# CLK_PWR.net
KiCad netlist of a schematic drawn in Altium Designer
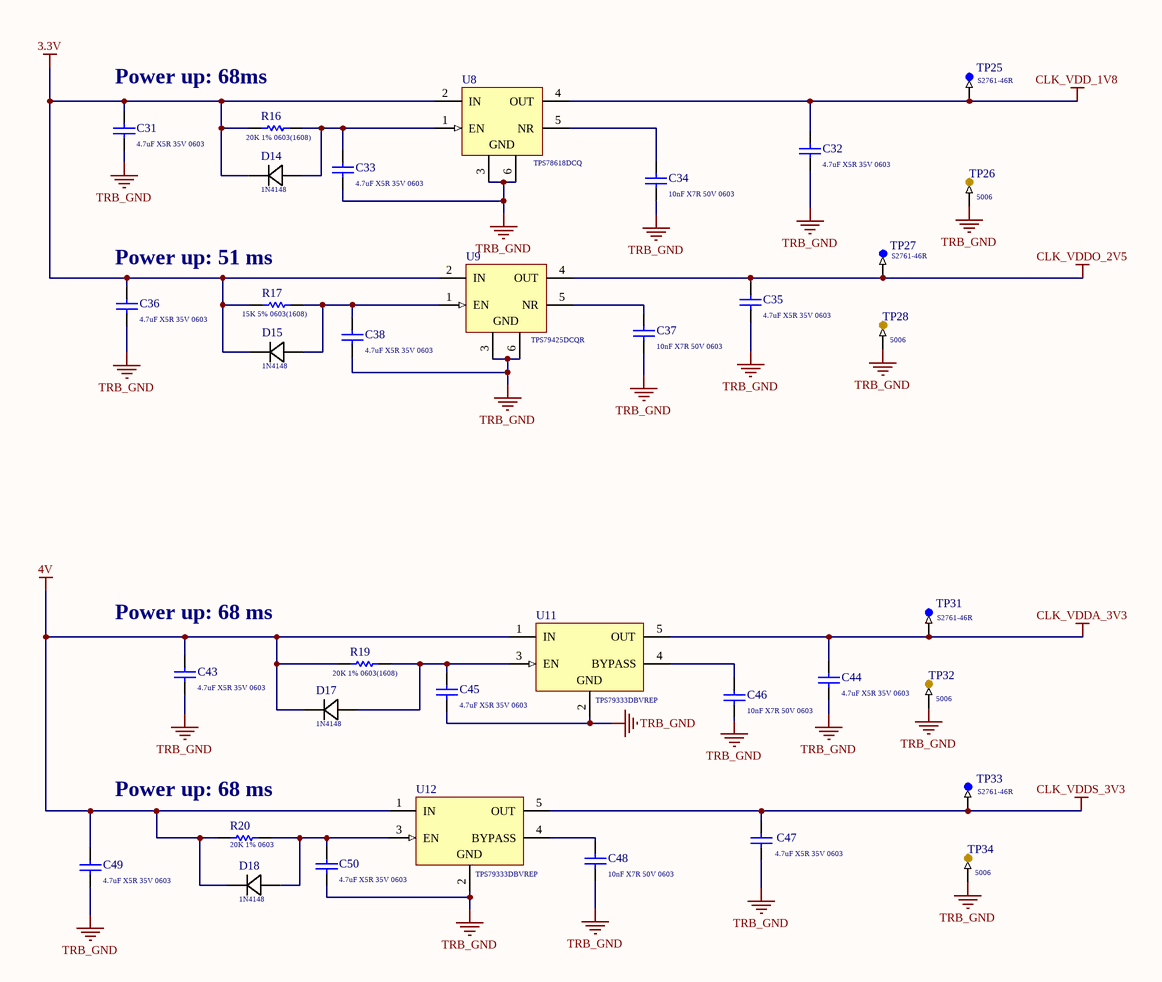
[diagram p0: CLK_PWR.SchDoc]

(export (version "E")
  (design (tool "Eeschema 10.0.6"))
  (components
    (comp (ref "C31")
      (value "Cap_Murata_ZRB18AR6YA475ME05L_4.7uF")
      (footprint "Cap_Murata_ZRB18AR6YA475ME05L_4.7uF")
      (description "CAP CER 4.7uF 35V X5R 0603")
      (fields (field (name "CAPACITANCE") "4.7uF X5R 35V 0603"))
      (libsource (lib "Cap_Murata_ZRB18AR6YA475ME05L_4.7uF") (part "Cap_Murata_ZRB18AR6YA475ME05L_4.7uF"))
    )
    (comp (ref "C32")
      (value "Cap_Murata_ZRB18AR6YA475ME05L_4.7uF")
      (footprint "Cap_Murata_ZRB18AR6YA475ME05L_4.7uF")
      (description "CAP CER 4.7uF 35V X5R 0603")
      (fields (field (name "CAPACITANCE") "4.7uF X5R 35V 0603"))
      (libsource (lib "Cap_Murata_ZRB18AR6YA475ME05L_4.7uF") (part "Cap_Murata_ZRB18AR6YA475ME05L_4.7uF"))
    )
    (comp (ref "C33")
      (value "Cap_Murata_ZRB18AR6YA475ME05L_4.7uF")
      (footprint "Cap_Murata_ZRB18AR6YA475ME05L_4.7uF")
      (description "CAP CER 4.7uF 35V X5R 0603")
      (fields (field (name "CAPACITANCE") "4.7uF X5R 35V 0603"))
      (libsource (lib "Cap_Murata_ZRB18AR6YA475ME05L_4.7uF") (part "Cap_Murata_ZRB18AR6YA475ME05L_4.7uF"))
    )
    (comp (ref "C34")
      (value "Cap_Kemet_C0603C103J5RACTU_eec")
      (footprint "Kemet_C0603_0")
      (description "CAP CER 10nF 50V X7R 0603")
      (fields
        (field (name "PART NUMBER") "C0603C103J5RACTU")
        (field (name "MANUFACTURER") "Kemet")
        (field (name "CAPACITANCE") "10nF X7R 50V 0603")
      )
      (libsource (lib "Cap_Kemet_C0603C103J5RACTU_10nF") (part "Cap_Kemet_C0603C103J5RACTU_eec"))
    )
    (comp (ref "C35")
      (value "Cap_Murata_ZRB18AR6YA475ME05L_4.7uF")
      (footprint "Cap_Murata_ZRB18AR6YA475ME05L_4.7uF")
      (description "CAP CER 4.7uF 35V X5R 0603")
      (fields (field (name "CAPACITANCE") "4.7uF X5R 35V 0603"))
      (libsource (lib "Cap_Murata_ZRB18AR6YA475ME05L_4.7uF") (part "Cap_Murata_ZRB18AR6YA475ME05L_4.7uF"))
    )
    (comp (ref "C36")
      (value "Cap_Murata_ZRB18AR6YA475ME05L_4.7uF")
      (footprint "Cap_Murata_ZRB18AR6YA475ME05L_4.7uF")
      (description "CAP CER 4.7uF 35V X5R 0603")
      (fields (field (name "CAPACITANCE") "4.7uF X5R 35V 0603"))
      (libsource (lib "Cap_Murata_ZRB18AR6YA475ME05L_4.7uF") (part "Cap_Murata_ZRB18AR6YA475ME05L_4.7uF"))
    )
    (comp (ref "C37")
      (value "Cap_Kemet_C0603C103J5RACTU_eec")
      (footprint "Kemet_C0603_0")
      (description "CAP CER 10nF 50V X7R 0603")
      (fields
        (field (name "PART NUMBER") "C0603C103J5RACTU")
        (field (name "MANUFACTURER") "Kemet")
        (field (name "CAPACITANCE") "10nF X7R 50V 0603")
      )
      (libsource (lib "Cap_Kemet_C0603C103J5RACTU_10nF") (part "Cap_Kemet_C0603C103J5RACTU_eec"))
    )
    (comp (ref "C38")
      (value "Cap_Murata_ZRB18AR6YA475ME05L_4.7uF")
      (footprint "Cap_Murata_ZRB18AR6YA475ME05L_4.7uF")
      (description "CAP CER 4.7uF 35V X5R 0603")
      (fields (field (name "CAPACITANCE") "4.7uF X5R 35V 0603"))
      (libsource (lib "Cap_Murata_ZRB18AR6YA475ME05L_4.7uF") (part "Cap_Murata_ZRB18AR6YA475ME05L_4.7uF"))
    )
    (comp (ref "C43")
      (value "Cap_Murata_ZRB18AR6YA475ME05L_4.7uF")
      (footprint "Cap_Murata_ZRB18AR6YA475ME05L_4.7uF")
      (description "CAP CER 4.7uF 35V X5R 0603")
      (fields (field (name "CAPACITANCE") "4.7uF X5R 35V 0603"))
      (libsource (lib "Cap_Murata_ZRB18AR6YA475ME05L_4.7uF") (part "Cap_Murata_ZRB18AR6YA475ME05L_4.7uF"))
    )
    (comp (ref "C44")
      (value "Cap_Murata_ZRB18AR6YA475ME05L_4.7uF")
      (footprint "Cap_Murata_ZRB18AR6YA475ME05L_4.7uF")
      (description "CAP CER 4.7uF 35V X5R 0603")
      (fields (field (name "CAPACITANCE") "4.7uF X5R 35V 0603"))
      (libsource (lib "Cap_Murata_ZRB18AR6YA475ME05L_4.7uF") (part "Cap_Murata_ZRB18AR6YA475ME05L_4.7uF"))
    )
    (comp (ref "C45")
      (value "Cap_Murata_ZRB18AR6YA475ME05L_4.7uF")
      (footprint "Cap_Murata_ZRB18AR6YA475ME05L_4.7uF")
      (description "CAP CER 4.7uF 35V X5R 0603")
      (fields (field (name "CAPACITANCE") "4.7uF X5R 35V 0603"))
      (libsource (lib "Cap_Murata_ZRB18AR6YA475ME05L_4.7uF") (part "Cap_Murata_ZRB18AR6YA475ME05L_4.7uF"))
    )
    (comp (ref "C46")
      (value "Cap_Kemet_C0603C103J5RACTU_eec")
      (footprint "Kemet_C0603_0")
      (description "CAP CER 10nF 50V X7R 0603")
      (fields
        (field (name "PART NUMBER") "C0603C103J5RACTU")
        (field (name "MANUFACTURER") "Kemet")
        (field (name "CAPACITANCE") "10nF X7R 50V 0603")
      )
      (libsource (lib "Cap_Kemet_C0603C103J5RACTU_10nF") (part "Cap_Kemet_C0603C103J5RACTU_eec"))
    )
    (comp (ref "C47")
      (value "Cap_Murata_ZRB18AR6YA475ME05L_4.7uF")
      (footprint "Cap_Murata_ZRB18AR6YA475ME05L_4.7uF")
      (description "CAP CER 4.7uF 35V X5R 0603")
      (fields (field (name "CAPACITANCE") "4.7uF X5R 35V 0603"))
      (libsource (lib "Cap_Murata_ZRB18AR6YA475ME05L_4.7uF") (part "Cap_Murata_ZRB18AR6YA475ME05L_4.7uF"))
    )
    (comp (ref "C48")
      (value "Cap_Kemet_C0603C103J5RACTU_eec")
      (footprint "Kemet_C0603_0")
      (description "CAP CER 10nF 50V X7R 0603")
      (fields
        (field (name "PART NUMBER") "C0603C103J5RACTU")
        (field (name "MANUFACTURER") "Kemet")
        (field (name "CAPACITANCE") "10nF X7R 50V 0603")
      )
      (libsource (lib "Cap_Kemet_C0603C103J5RACTU_10nF") (part "Cap_Kemet_C0603C103J5RACTU_eec"))
    )
    (comp (ref "C49")
      (value "Cap_Murata_ZRB18AR6YA475ME05L_4.7uF")
      (footprint "Cap_Murata_ZRB18AR6YA475ME05L_4.7uF")
      (description "CAP CER 4.7uF 35V X5R 0603")
      (fields (field (name "CAPACITANCE") "4.7uF X5R 35V 0603"))
      (libsource (lib "Cap_Murata_ZRB18AR6YA475ME05L_4.7uF") (part "Cap_Murata_ZRB18AR6YA475ME05L_4.7uF"))
    )
    (comp (ref "C50")
      (value "Cap_Murata_ZRB18AR6YA475ME05L_4.7uF")
      (footprint "Cap_Murata_ZRB18AR6YA475ME05L_4.7uF")
      (description "CAP CER 4.7uF 35V X5R 0603")
      (fields (field (name "CAPACITANCE") "4.7uF X5R 35V 0603"))
      (libsource (lib "Cap_Murata_ZRB18AR6YA475ME05L_4.7uF") (part "Cap_Murata_ZRB18AR6YA475ME05L_4.7uF"))
    )
    (comp (ref "D14")
      (value "Diode_ON_Semiconductor_1N4148WT_300mA")
      (footprint "Diode_ON_Semiconductor_1N4148WT_300mA")
      (description "Diodes - General Purpose, Power, Switching SINGLE JUNC. 75V 4.0NS COMP")
      (fields (field (name "SERIES") "1N4148"))
      (libsource (lib "Diode_ON_Semiconductor_1N4148WT_300mA") (part "Diode_ON_Semiconductor_1N4148WT_300mA"))
    )
    (comp (ref "D15")
      (value "Diode_ON_Semiconductor_1N4148WT_300mA")
      (footprint "Diode_ON_Semiconductor_1N4148WT_300mA")
      (description "Diodes - General Purpose, Power, Switching SINGLE JUNC. 75V 4.0NS COMP")
      (fields (field (name "SERIES") "1N4148"))
      (libsource (lib "Diode_ON_Semiconductor_1N4148WT_300mA") (part "Diode_ON_Semiconductor_1N4148WT_300mA"))
    )
    (comp (ref "D17")
      (value "Diode_ON_Semiconductor_1N4148WT_300mA")
      (footprint "Diode_ON_Semiconductor_1N4148WT_300mA")
      (description "Diodes - General Purpose, Power, Switching SINGLE JUNC. 75V 4.0NS COMP")
      (fields (field (name "SERIES") "1N4148"))
      (libsource (lib "Diode_ON_Semiconductor_1N4148WT_300mA") (part "Diode_ON_Semiconductor_1N4148WT_300mA"))
    )
    (comp (ref "D18")
      (value "Diode_ON_Semiconductor_1N4148WT_300mA")
      (footprint "Diode_ON_Semiconductor_1N4148WT_300mA")
      (description "Diodes - General Purpose, Power, Switching SINGLE JUNC. 75V 4.0NS COMP")
      (fields (field (name "SERIES") "1N4148"))
      (libsource (lib "Diode_ON_Semiconductor_1N4148WT_300mA") (part "Diode_ON_Semiconductor_1N4148WT_300mA"))
    )
    (comp (ref "R16")
      (value "20K 1% 0603(1608)")
      (footprint "RESC0603(1608)_M")
      (description "20K 0.1W 1% 0603 (1608 Metric)  SMD")
      (fields (field (name "POWER") "0.1 W") (field (name "TOLERANCE") "1 %"))
      (libsource (lib "Altium Content Vault") (part "RES"))
    )
    (comp (ref "R17")
      (value "15K 5% 0603(1608)")
      (footprint "RESC0603(1608)_M")
      (description "15K 0.1W 5% 0603 (1608 Metric)  SMD")
      (fields (field (name "TOLERANCE") "5 %") (field (name "POWER") "0.1 W"))
      (libsource (lib "Altium Content Vault") (part "RES"))
    )
    (comp (ref "R19")
      (value "20K 1% 0603(1608)")
      (footprint "RESC0603(1608)_M")
      (description "20K 0.1W 1% 0603 (1608 Metric)  SMD")
      (fields (field (name "POWER") "0.1 W") (field (name "TOLERANCE") "1 %"))
      (libsource (lib "Altium Content Vault") (part "RES"))
    )
    (comp (ref "R20")
      (value "20K 1% 0603")
      (footprint "RESC0603(1608)_M")
      (description "20K 0.1W 1% 0603 (1608 Metric)  SMD")
      (fields (field (name "TOLERANCE") "1 %") (field (name "POWER") "0.1 W"))
      (libsource (lib "Altium Content Vault") (part "RES"))
    )
    (comp (ref "TP25")
      (value "TP_Harwin_S2761_46R")
      (footprint "TP_Harwin_S2761_46R")
      (description "Circuit Board Hardware - PCB SMT Mini Test Terminal, Reel")
      (fields (field (name "SERIES") "S2761-46R"))
      (libsource (lib "TP_Harwin_S2761_46R") (part "TP_Harwin_S2761_46R"))
    )
    (comp (ref "TP26")
      (value "TP_Keystone_Electronics_5006")
      (footprint "TP_Keystone_Electronics_5006")
      (description "Circuit Board Hardware - PCB TEST POINT BLK .063")
      (fields (field (name "SERIES") "5006"))
      (libsource (lib "TP_Keystone_Electronics_5006") (part "TP_Keystone_Electronics_5006"))
    )
    (comp (ref "TP27")
      (value "TP_Harwin_S2761_46R")
      (footprint "TP_Harwin_S2761_46R")
      (description "Circuit Board Hardware - PCB SMT Mini Test Terminal, Reel")
      (fields (field (name "SERIES") "S2761-46R"))
      (libsource (lib "TP_Harwin_S2761_46R") (part "TP_Harwin_S2761_46R"))
    )
    (comp (ref "TP28")
      (value "TP_Keystone_Electronics_5006")
      (footprint "TP_Keystone_Electronics_5006")
      (description "Circuit Board Hardware - PCB TEST POINT BLK .063")
      (fields (field (name "SERIES") "5006"))
      (libsource (lib "TP_Keystone_Electronics_5006") (part "TP_Keystone_Electronics_5006"))
    )
    (comp (ref "TP31")
      (value "TP_Harwin_S2761_46R")
      (footprint "TP_Harwin_S2761_46R")
      (description "Circuit Board Hardware - PCB SMT Mini Test Terminal, Reel")
      (fields (field (name "SERIES") "S2761-46R"))
      (libsource (lib "TP_Harwin_S2761_46R") (part "TP_Harwin_S2761_46R"))
    )
    (comp (ref "TP32")
      (value "TP_Keystone_Electronics_5006")
      (footprint "TP_Keystone_Electronics_5006")
      (description "Circuit Board Hardware - PCB TEST POINT BLK .063")
      (fields (field (name "SERIES") "5006"))
      (libsource (lib "TP_Keystone_Electronics_5006") (part "TP_Keystone_Electronics_5006"))
    )
    (comp (ref "TP33")
      (value "TP_Harwin_S2761_46R")
      (footprint "TP_Harwin_S2761_46R")
      (description "Circuit Board Hardware - PCB SMT Mini Test Terminal, Reel")
      (fields (field (name "SERIES") "S2761-46R"))
      (libsource (lib "TP_Harwin_S2761_46R") (part "TP_Harwin_S2761_46R"))
    )
    (comp (ref "TP34")
      (value "TP_Keystone_Electronics_5006")
      (footprint "TP_Keystone_Electronics_5006")
      (description "Circuit Board Hardware - PCB TEST POINT BLK .063")
      (fields (field (name "SERIES") "5006"))
      (libsource (lib "TP_Keystone_Electronics_5006") (part "TP_Keystone_Electronics_5006"))
    )
    (comp (ref "U8")
      (value "TPS78618DCQ")
      (footprint "DCQ0006A_L")
      (fields (field (name "MANUFACTURER") "Texas Instruments"))
      (libsource (lib "Altium Content Vault") (part "TI-TPS7XXXXXXXX"))
    )
    (comp (ref "U9")
      (value "TPS79425DCQR")
      (footprint "DCQ0006A_L")
      (fields (field (name "MANUFACTURER") "Texas Instruments"))
      (libsource (lib "Altium Content Vault") (part "TI-TPS7XXXXXXXX"))
    )
    (comp (ref "U11")
      (value "TPS79333DBVREP")
      (footprint "DBV0005A_M")
      (fields (field (name "MANUFACTURER") "Texas Instruments"))
      (libsource (lib "TPS79333DBVREP") (part "CMP-0394-00316-2"))
    )
    (comp (ref "U12")
      (value "TPS79333DBVREP")
      (footprint "DBV0005A_M")
      (fields (field (name "MANUFACTURER") "Texas Instruments"))
      (libsource (lib "TPS79333DBVREP") (part "CMP-0394-00316-2"))
    )
  )
  (nets
    (net (code "1") (name "3.3V") (class "Default")
      (node (ref "C31") (pin "2") (pinfunction "2_2") (pintype "passive"))
      (node (ref "C36") (pin "2") (pinfunction "2_2") (pintype "passive"))
      (node (ref "D14") (pin "1") (pinfunction "1_1") (pintype "passive"))
      (node (ref "D15") (pin "1") (pinfunction "1_1") (pintype "passive"))
      (node (ref "R16") (pin "1") (pinfunction "1_1") (pintype "passive"))
      (node (ref "R17") (pin "1") (pinfunction "1_1") (pintype "passive"))
      (node (ref "U8") (pin "2") (pinfunction "IN_2") (pintype "power_in"))
      (node (ref "U9") (pin "2") (pinfunction "IN_2") (pintype "power_in"))
    )
    (net (code "2") (name "4V") (class "Default")
      (node (ref "C43") (pin "2") (pinfunction "2_2") (pintype "passive"))
      (node (ref "C49") (pin "2") (pinfunction "2_2") (pintype "passive"))
      (node (ref "D17") (pin "1") (pinfunction "1_1") (pintype "passive"))
      (node (ref "D18") (pin "1") (pinfunction "1_1") (pintype "passive"))
      (node (ref "R19") (pin "1") (pinfunction "1_1") (pintype "passive"))
      (node (ref "R20") (pin "2") (pinfunction "2_2") (pintype "passive"))
      (node (ref "U11") (pin "1") (pinfunction "IN_1") (pintype "power_in"))
      (node (ref "U12") (pin "1") (pinfunction "IN_1") (pintype "power_in"))
    )
    (net (code "3") (name "CLK_VDDA_3V3") (class "Default")
      (node (ref "C44") (pin "2") (pinfunction "2_2") (pintype "passive"))
      (node (ref "TP31") (pin "1") (pinfunction "1_1") (pintype "input"))
      (node (ref "U11") (pin "5") (pinfunction "OUT_5") (pintype "power_in"))
    )
    (net (code "4") (name "CLK_VDDO_2V5") (class "Default")
      (node (ref "C35") (pin "2") (pinfunction "2_2") (pintype "passive"))
      (node (ref "TP27") (pin "1") (pinfunction "1_1") (pintype "input"))
      (node (ref "U9") (pin "4") (pinfunction "OUT_4") (pintype "power_in"))
    )
    (net (code "5") (name "CLK_VDDS_3V3") (class "Default")
      (node (ref "C47") (pin "2") (pinfunction "2_2") (pintype "passive"))
      (node (ref "TP33") (pin "1") (pinfunction "1_1") (pintype "input"))
      (node (ref "U12") (pin "5") (pinfunction "OUT_5") (pintype "power_in"))
    )
    (net (code "6") (name "CLK_VDD_1V8") (class "Default")
      (node (ref "C32") (pin "2") (pinfunction "2_2") (pintype "passive"))
      (node (ref "TP25") (pin "1") (pinfunction "1_1") (pintype "input"))
      (node (ref "U8") (pin "4") (pinfunction "OUT_4") (pintype "power_in"))
    )
    (net (code "7") (name "Net-(U8-EN)") (class "Default")
      (node (ref "C33") (pin "2") (pinfunction "2_2") (pintype "passive"))
      (node (ref "D14") (pin "2") (pinfunction "2_2") (pintype "passive"))
      (node (ref "R16") (pin "2") (pinfunction "2_2") (pintype "passive"))
      (node (ref "U8") (pin "1") (pinfunction "EN_1") (pintype "input"))
    )
    (net (code "8") (name "Net-(U8-NR)") (class "Default")
      (node (ref "C34") (pin "1") (pinfunction "1_1") (pintype "passive"))
      (node (ref "U8") (pin "5") (pinfunction "NR_5") (pintype "passive"))
    )
    (net (code "9") (name "Net-(U9-EN)") (class "Default")
      (node (ref "C38") (pin "2") (pinfunction "2_2") (pintype "passive"))
      (node (ref "D15") (pin "2") (pinfunction "2_2") (pintype "passive"))
      (node (ref "R17") (pin "2") (pinfunction "2_2") (pintype "passive"))
      (node (ref "U9") (pin "1") (pinfunction "EN_1") (pintype "input"))
    )
    (net (code "10") (name "Net-(U9-NR)") (class "Default")
      (node (ref "C37") (pin "1") (pinfunction "1_1") (pintype "passive"))
      (node (ref "U9") (pin "5") (pinfunction "NR_5") (pintype "passive"))
    )
    (net (code "11") (name "Net-(U11-BYPASS)") (class "Default")
      (node (ref "C46") (pin "1") (pinfunction "1_1") (pintype "passive"))
      (node (ref "U11") (pin "4") (pinfunction "BYPASS_4") (pintype "passive"))
    )
    (net (code "12") (name "Net-(U11-EN)") (class "Default")
      (node (ref "C45") (pin "2") (pinfunction "2_2") (pintype "passive"))
      (node (ref "D17") (pin "2") (pinfunction "2_2") (pintype "passive"))
      (node (ref "R19") (pin "2") (pinfunction "2_2") (pintype "passive"))
      (node (ref "U11") (pin "3") (pinfunction "EN_3") (pintype "input"))
    )
    (net (code "13") (name "Net-(U12-BYPASS)") (class "Default")
      (node (ref "C48") (pin "1") (pinfunction "1_1") (pintype "passive"))
      (node (ref "U12") (pin "4") (pinfunction "BYPASS_4") (pintype "passive"))
    )
    (net (code "14") (name "Net-(U12-EN)") (class "Default")
      (node (ref "C50") (pin "2") (pinfunction "2_2") (pintype "passive"))
      (node (ref "D18") (pin "2") (pinfunction "2_2") (pintype "passive"))
      (node (ref "R20") (pin "1") (pinfunction "1_1") (pintype "passive"))
      (node (ref "U12") (pin "3") (pinfunction "EN_3") (pintype "input"))
    )
    (net (code "15") (name "TRB_GND") (class "Default")
      (node (ref "C31") (pin "1") (pinfunction "1_1") (pintype "passive"))
      (node (ref "C32") (pin "1") (pinfunction "1_1") (pintype "passive"))
      (node (ref "C33") (pin "1") (pinfunction "1_1") (pintype "passive"))
      (node (ref "C34") (pin "2") (pinfunction "2_2") (pintype "passive"))
      (node (ref "C35") (pin "1") (pinfunction "1_1") (pintype "passive"))
      (node (ref "C36") (pin "1") (pinfunction "1_1") (pintype "passive"))
      (node (ref "C37") (pin "2") (pinfunction "2_2") (pintype "passive"))
      (node (ref "C38") (pin "1") (pinfunction "1_1") (pintype "passive"))
      (node (ref "C43") (pin "1") (pinfunction "1_1") (pintype "passive"))
      (node (ref "C44") (pin "1") (pinfunction "1_1") (pintype "passive"))
      (node (ref "C45") (pin "1") (pinfunction "1_1") (pintype "passive"))
      (node (ref "C46") (pin "2") (pinfunction "2_2") (pintype "passive"))
      (node (ref "C47") (pin "1") (pinfunction "1_1") (pintype "passive"))
      (node (ref "C48") (pin "2") (pinfunction "2_2") (pintype "passive"))
      (node (ref "C49") (pin "1") (pinfunction "1_1") (pintype "passive"))
      (node (ref "C50") (pin "1") (pinfunction "1_1") (pintype "passive"))
      (node (ref "TP26") (pin "1") (pinfunction "1_1") (pintype "input"))
      (node (ref "TP28") (pin "1") (pinfunction "1_1") (pintype "input"))
      (node (ref "TP32") (pin "1") (pinfunction "1_1") (pintype "input"))
      (node (ref "TP34") (pin "1") (pinfunction "1_1") (pintype "input"))
      (node (ref "U11") (pin "2") (pinfunction "GND_2") (pintype "power_in"))
      (node (ref "U12") (pin "2") (pinfunction "GND_2") (pintype "power_in"))
      (node (ref "U8") (pin "3") (pinfunction "GND_3") (pintype "power_in"))
      (node (ref "U8") (pin "6") (pinfunction "GND_6") (pintype "power_in"))
      (node (ref "U9") (pin "3") (pinfunction "GND_3") (pintype "power_in"))
      (node (ref "U9") (pin "6") (pinfunction "GND_6") (pintype "power_in"))
    )
  )
)
